# modular_expansion_system_audio_mixer.net
KiCad netlist of a schematic drawn in EAGLE
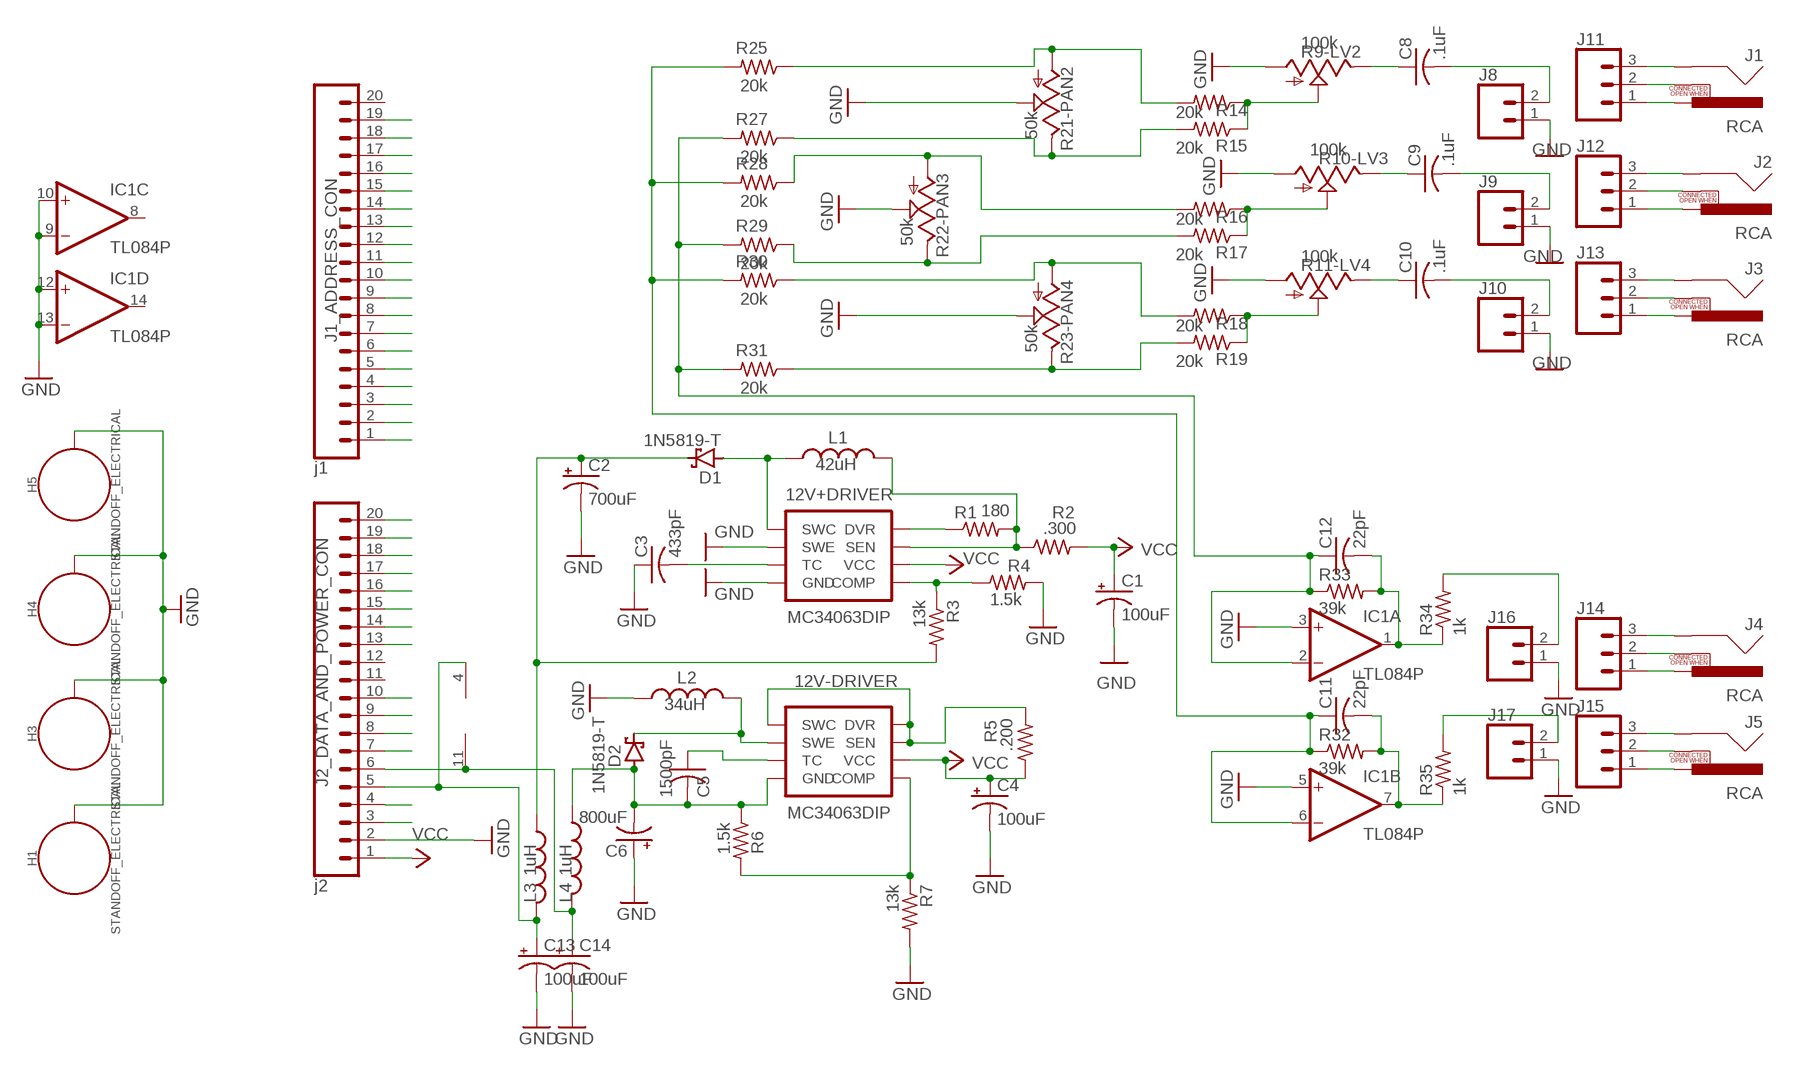
[diagram p0: schematic, sheet 1]

(export (version "E")
  (design (tool "Eeschema 10.0.6"))
  (components
    (comp (ref "12V+DRIVER")
      (value "MC34063DIP")
      (footprint "eagle-import:DIP-08")
      (libsource (lib "eagle-import") (part "MC34063DIP"))
    )
    (comp (ref "12V-DRIVER")
      (value "MC34063DIP")
      (footprint "eagle-import:DIP-08")
      (libsource (lib "eagle-import") (part "MC34063DIP"))
    )
    (comp (ref "C1")
      (value "100uF")
      (footprint "eagle-import:E2,5-5")
      (libsource (lib "eagle-import") (part "CPOL-USE2.5-5"))
    )
    (comp (ref "C2")
      (value "700uF")
      (footprint "eagle-import:E3,5-10")
      (libsource (lib "eagle-import") (part "CPOL-USE3.5-10"))
    )
    (comp (ref "C3")
      (value "433pF")
      (footprint "eagle-import:C025-040X050")
      (libsource (lib "eagle-import") (part "C-US025-040X050"))
    )
    (comp (ref "C4")
      (value "100uF")
      (footprint "eagle-import:E2,5-5")
      (libsource (lib "eagle-import") (part "CPOL-USE2.5-5"))
    )
    (comp (ref "C5")
      (value "1500pF")
      (footprint "eagle-import:C025-040X050")
      (libsource (lib "eagle-import") (part "C-US025-040X050"))
    )
    (comp (ref "C6")
      (value "800uF")
      (footprint "eagle-import:E3,5-10")
      (libsource (lib "eagle-import") (part "CPOL-USE3.5-10"))
    )
    (comp (ref "C8")
      (value ".1uF")
      (footprint "eagle-import:C025-024X044")
      (libsource (lib "eagle-import") (part "C-US025-024X044"))
    )
    (comp (ref "C9")
      (value ".1uF")
      (footprint "eagle-import:C025-024X044")
      (libsource (lib "eagle-import") (part "C-US025-024X044"))
    )
    (comp (ref "C10")
      (value ".1uF")
      (footprint "eagle-import:C025-024X044")
      (libsource (lib "eagle-import") (part "C-US025-024X044"))
    )
    (comp (ref "C11")
      (value "22pF")
      (footprint "eagle-import:C025-024X044")
      (libsource (lib "eagle-import") (part "C-US025-024X044"))
    )
    (comp (ref "C12")
      (value "22pF")
      (footprint "eagle-import:C025-024X044")
      (libsource (lib "eagle-import") (part "C-US025-024X044"))
    )
    (comp (ref "C13")
      (value "100uF")
      (footprint "eagle-import:E2,5-5")
      (libsource (lib "eagle-import") (part "CPOL-USE2.5-5"))
    )
    (comp (ref "C14")
      (value "100uF")
      (footprint "eagle-import:E2,5-5")
      (libsource (lib "eagle-import") (part "CPOL-USE2.5-5"))
    )
    (comp (ref "D1")
      (value "1N5819-T")
      (footprint "eagle-import:DO41-7.6")
      (libsource (lib "eagle-import") (part "1N5819-T"))
    )
    (comp (ref "D2")
      (value "1N5819-T")
      (footprint "eagle-import:DO41-7.6")
      (libsource (lib "eagle-import") (part "1N5819-T"))
    )
    (comp (ref "H1")
      (value "STANDOFF_ELECTRICAL")
      (footprint "eagle-import:STANDOFF-ELECTRICAL")
      (libsource (lib "eagle-import") (part "STANDOFF_ELECTRICAL"))
    )
    (comp (ref "H3")
      (value "STANDOFF_ELECTRICAL")
      (footprint "eagle-import:STANDOFF-ELECTRICAL")
      (libsource (lib "eagle-import") (part "STANDOFF_ELECTRICAL"))
    )
    (comp (ref "H4")
      (value "STANDOFF_ELECTRICAL")
      (footprint "eagle-import:STANDOFF-ELECTRICAL")
      (libsource (lib "eagle-import") (part "STANDOFF_ELECTRICAL"))
    )
    (comp (ref "H5")
      (value "STANDOFF_ELECTRICAL")
      (footprint "eagle-import:STANDOFF-ELECTRICAL")
      (libsource (lib "eagle-import") (part "STANDOFF_ELECTRICAL"))
    )
    (comp (ref "IC1")
      (value "TL084P")
      (footprint "eagle-import:DIL14")
      (libsource (lib "eagle-import") (part "TL084P"))
    )
    (comp (ref "J1")
      (value "RCA")
      (footprint "eagle-import:RCA")
      (libsource (lib "eagle-import") (part "RCA"))
    )
    (comp (ref "J1_ADDRESS_CON")
      (value "j1")
      (footprint "eagle-import:1X20")
      (libsource (lib "eagle-import") (part "CONN_20"))
    )
    (comp (ref "J2")
      (value "RCA")
      (footprint "eagle-import:RCA")
      (libsource (lib "eagle-import") (part "RCA"))
    )
    (comp (ref "J2_DATA_AND_POWER_CON")
      (value "j2")
      (footprint "eagle-import:1X20")
      (libsource (lib "eagle-import") (part "CONN_20"))
    )
    (comp (ref "J3")
      (value "RCA")
      (footprint "eagle-import:RCA")
      (libsource (lib "eagle-import") (part "RCA"))
    )
    (comp (ref "J4")
      (value "RCA")
      (footprint "eagle-import:RCA")
      (libsource (lib "eagle-import") (part "RCA"))
    )
    (comp (ref "J5")
      (value "RCA")
      (footprint "eagle-import:RCA")
      (libsource (lib "eagle-import") (part "RCA"))
    )
    (comp (ref "J8")
      (value "CONN_02")
      (footprint "eagle-import:1X02")
      (libsource (lib "eagle-import") (part "CONN_02"))
    )
    (comp (ref "J9")
      (value "CONN_02")
      (footprint "eagle-import:1X02")
      (libsource (lib "eagle-import") (part "CONN_02"))
    )
    (comp (ref "J10")
      (value "CONN_02")
      (footprint "eagle-import:1X02")
      (libsource (lib "eagle-import") (part "CONN_02"))
    )
    (comp (ref "J11")
      (value "CONN_03")
      (footprint "eagle-import:1X03")
      (libsource (lib "eagle-import") (part "CONN_03"))
    )
    (comp (ref "J12")
      (value "CONN_03")
      (footprint "eagle-import:1X03")
      (libsource (lib "eagle-import") (part "CONN_03"))
    )
    (comp (ref "J13")
      (value "CONN_03")
      (footprint "eagle-import:1X03")
      (libsource (lib "eagle-import") (part "CONN_03"))
    )
    (comp (ref "J14")
      (value "CONN_03")
      (footprint "eagle-import:1X03")
      (libsource (lib "eagle-import") (part "CONN_03"))
    )
    (comp (ref "J15")
      (value "CONN_03")
      (footprint "eagle-import:1X03")
      (libsource (lib "eagle-import") (part "CONN_03"))
    )
    (comp (ref "J16")
      (value "CONN_02")
      (footprint "eagle-import:1X02")
      (libsource (lib "eagle-import") (part "CONN_02"))
    )
    (comp (ref "J17")
      (value "CONN_02")
      (footprint "eagle-import:1X02")
      (libsource (lib "eagle-import") (part "CONN_02"))
    )
    (comp (ref "L1")
      (value "42uH")
      (footprint "eagle-import:0207_7")
      (libsource (lib "eagle-import") (part "resistor_348_L-US0207/7"))
    )
    (comp (ref "L2")
      (value "34uH")
      (footprint "eagle-import:0207_7")
      (libsource (lib "eagle-import") (part "resistor_348_L-US0207/7"))
    )
    (comp (ref "L3")
      (value "1uH")
      (footprint "eagle-import:0207_5V")
      (libsource (lib "eagle-import") (part "L-US0207/5V"))
    )
    (comp (ref "L4")
      (value "1uH")
      (footprint "eagle-import:0207_5V")
      (libsource (lib "eagle-import") (part "L-US0207/5V"))
    )
    (comp (ref "R1")
      (value "180")
      (footprint "eagle-import:0204V")
      (libsource (lib "eagle-import") (part "R-US_0204/2V"))
    )
    (comp (ref "R2")
      (value ".300")
      (footprint "eagle-import:0204V")
      (libsource (lib "eagle-import") (part "R-US_0204/2V"))
    )
    (comp (ref "R3")
      (value "13k")
      (footprint "eagle-import:0204V")
      (libsource (lib "eagle-import") (part "R-US_0204/2V"))
    )
    (comp (ref "R4")
      (value "1.5k")
      (footprint "eagle-import:0204V")
      (libsource (lib "eagle-import") (part "R-US_0204/2V"))
    )
    (comp (ref "R5")
      (value ".200")
      (footprint "eagle-import:0204V")
      (libsource (lib "eagle-import") (part "R-US_0204/2V"))
    )
    (comp (ref "R6")
      (value "1.5k")
      (footprint "eagle-import:0204V")
      (libsource (lib "eagle-import") (part "R-US_0204/2V"))
    )
    (comp (ref "R7")
      (value "13k")
      (footprint "eagle-import:0204V")
      (libsource (lib "eagle-import") (part "R-US_0204/2V"))
    )
    (comp (ref "R9-LV2")
      (value "100k")
      (footprint "eagle-import:B25U")
      (libsource (lib "eagle-import") (part "TRIM_US-B25U"))
    )
    (comp (ref "R10-LV3")
      (value "100k")
      (footprint "eagle-import:B25U")
      (libsource (lib "eagle-import") (part "TRIM_US-B25U"))
    )
    (comp (ref "R11-LV4")
      (value "100k")
      (footprint "eagle-import:B25U")
      (libsource (lib "eagle-import") (part "TRIM_US-B25U"))
    )
    (comp (ref "R14")
      (value "20k")
      (footprint "eagle-import:0204V")
      (libsource (lib "eagle-import") (part "R-US_0204/2V"))
    )
    (comp (ref "R15")
      (value "20k")
      (footprint "eagle-import:0204V")
      (libsource (lib "eagle-import") (part "R-US_0204/2V"))
    )
    (comp (ref "R16")
      (value "20k")
      (footprint "eagle-import:0204V")
      (libsource (lib "eagle-import") (part "R-US_0204/2V"))
    )
    (comp (ref "R17")
      (value "20k")
      (footprint "eagle-import:0204V")
      (libsource (lib "eagle-import") (part "R-US_0204/2V"))
    )
    (comp (ref "R18")
      (value "20k")
      (footprint "eagle-import:0204V")
      (libsource (lib "eagle-import") (part "R-US_0204/2V"))
    )
    (comp (ref "R19")
      (value "20k")
      (footprint "eagle-import:0204V")
      (libsource (lib "eagle-import") (part "R-US_0204/2V"))
    )
    (comp (ref "R21-PAN2")
      (value "50k")
      (footprint "eagle-import:B25U")
      (libsource (lib "eagle-import") (part "TRIM_US-B25U"))
    )
    (comp (ref "R22-PAN3")
      (value "50k")
      (footprint "eagle-import:B25U")
      (libsource (lib "eagle-import") (part "TRIM_US-B25U"))
    )
    (comp (ref "R23-PAN4")
      (value "50k")
      (footprint "eagle-import:B25U")
      (libsource (lib "eagle-import") (part "TRIM_US-B25U"))
    )
    (comp (ref "R25")
      (value "20k")
      (footprint "eagle-import:0204V")
      (libsource (lib "eagle-import") (part "R-US_0204/2V"))
    )
    (comp (ref "R27")
      (value "20k")
      (footprint "eagle-import:0204V")
      (libsource (lib "eagle-import") (part "R-US_0204/2V"))
    )
    (comp (ref "R28")
      (value "20k")
      (footprint "eagle-import:0204V")
      (libsource (lib "eagle-import") (part "R-US_0204/2V"))
    )
    (comp (ref "R29")
      (value "20k")
      (footprint "eagle-import:0204V")
      (libsource (lib "eagle-import") (part "R-US_0204/2V"))
    )
    (comp (ref "R30")
      (value "20k")
      (footprint "eagle-import:0204V")
      (libsource (lib "eagle-import") (part "R-US_0204/2V"))
    )
    (comp (ref "R31")
      (value "20k")
      (footprint "eagle-import:0204V")
      (libsource (lib "eagle-import") (part "R-US_0204/2V"))
    )
    (comp (ref "R32")
      (value "39k")
      (footprint "eagle-import:0204V")
      (libsource (lib "eagle-import") (part "R-US_0204/2V"))
    )
    (comp (ref "R33")
      (value "39k")
      (footprint "eagle-import:0204V")
      (libsource (lib "eagle-import") (part "R-US_0204/2V"))
    )
    (comp (ref "R34")
      (value "1k")
      (footprint "eagle-import:0204V")
      (libsource (lib "eagle-import") (part "R-US_0204/2V"))
    )
    (comp (ref "R35")
      (value "1k")
      (footprint "eagle-import:0204V")
      (libsource (lib "eagle-import") (part "R-US_0204/2V"))
    )
  )
  (nets
    (net (code "1") (name "GND") (class "Default")
      (node (ref "12V+DRIVER") (pin "2") (pinfunction "SWE_2") (pintype "bidirectional"))
      (node (ref "12V+DRIVER") (pin "4") (pinfunction "GND_4") (pintype "bidirectional"))
      (node (ref "C1") (pin "-") (pinfunction "-_-") (pintype "passive"))
      (node (ref "C13") (pin "-") (pinfunction "-_-") (pintype "passive"))
      (node (ref "C14") (pin "-") (pinfunction "-_-") (pintype "passive"))
      (node (ref "C2") (pin "-") (pinfunction "-_-") (pintype "passive"))
      (node (ref "C3") (pin "1") (pinfunction "1_1") (pintype "passive"))
      (node (ref "C4") (pin "-") (pinfunction "-_-") (pintype "passive"))
      (node (ref "C6") (pin "+") (pinfunction "+_+") (pintype "passive"))
      (node (ref "H1") (pin "P1") (pinfunction "P$1_P1") (pintype "bidirectional"))
      (node (ref "H3") (pin "P1") (pinfunction "P$1_P1") (pintype "bidirectional"))
      (node (ref "H4") (pin "P1") (pinfunction "P$1_P1") (pintype "bidirectional"))
      (node (ref "H5") (pin "P1") (pinfunction "P$1_P1") (pintype "bidirectional"))
      (node (ref "IC1") (pin "10") (pinfunction "+IN_10") (pintype "input"))
      (node (ref "IC1") (pin "12") (pinfunction "+IN_12") (pintype "input"))
      (node (ref "IC1") (pin "13") (pinfunction "-IN_13") (pintype "input"))
      (node (ref "IC1") (pin "3") (pinfunction "+IN_3") (pintype "input"))
      (node (ref "IC1") (pin "5") (pinfunction "+IN_5") (pintype "input"))
      (node (ref "IC1") (pin "9") (pinfunction "-IN_9") (pintype "input"))
      (node (ref "J10") (pin "1") (pinfunction "1_1") (pintype "passive"))
      (node (ref "J16") (pin "1") (pinfunction "1_1") (pintype "passive"))
      (node (ref "J17") (pin "1") (pinfunction "1_1") (pintype "passive"))
      (node (ref "J2_DATA_AND_POWER_CON") (pin "2") (pinfunction "2_2") (pintype "passive"))
      (node (ref "J8") (pin "1") (pinfunction "1_1") (pintype "passive"))
      (node (ref "J9") (pin "1") (pinfunction "1_1") (pintype "passive"))
      (node (ref "L2") (pin "1") (pinfunction "1_1") (pintype "passive"))
      (node (ref "R10-LV3") (pin "A") (pinfunction "A_A") (pintype "passive"))
      (node (ref "R11-LV4") (pin "A") (pinfunction "A_A") (pintype "passive"))
      (node (ref "R21-PAN2") (pin "S") (pinfunction "S_S") (pintype "passive"))
      (node (ref "R22-PAN3") (pin "S") (pinfunction "S_S") (pintype "passive"))
      (node (ref "R23-PAN4") (pin "S") (pinfunction "S_S") (pintype "passive"))
      (node (ref "R4") (pin "2") (pinfunction "2_2") (pintype "passive"))
      (node (ref "R7") (pin "2") (pinfunction "2_2") (pintype "passive"))
      (node (ref "R9-LV2") (pin "A") (pinfunction "A_A") (pintype "passive"))
    )
    (net (code "2") (name "Net-(12V+DRIVER-COMP)") (class "Default")
      (node (ref "12V+DRIVER") (pin "5") (pinfunction "COMP_5") (pintype "bidirectional"))
      (node (ref "R3") (pin "1") (pinfunction "1_1") (pintype "passive"))
      (node (ref "R4") (pin "1") (pinfunction "1_1") (pintype "passive"))
    )
    (net (code "3") (name "Net-(12V+DRIVER-DVR)") (class "Default")
      (node (ref "12V+DRIVER") (pin "8") (pinfunction "DVR_8") (pintype "bidirectional"))
      (node (ref "R1") (pin "1") (pinfunction "1_1") (pintype "passive"))
    )
    (net (code "4") (name "Net-(12V+DRIVER-SEN)") (class "Default")
      (node (ref "12V+DRIVER") (pin "7") (pinfunction "SEN_7") (pintype "bidirectional"))
      (node (ref "L1") (pin "2") (pinfunction "2_2") (pintype "passive"))
      (node (ref "R1") (pin "2") (pinfunction "2_2") (pintype "passive"))
      (node (ref "R2") (pin "1") (pinfunction "1_1") (pintype "passive"))
    )
    (net (code "5") (name "Net-(12V+DRIVER-SWC)") (class "Default")
      (node (ref "12V+DRIVER") (pin "1") (pinfunction "SWC_1") (pintype "bidirectional"))
      (node (ref "D1") (pin "A") (pinfunction "A_A") (pintype "passive"))
      (node (ref "L1") (pin "1") (pinfunction "1_1") (pintype "passive"))
    )
    (net (code "6") (name "Net-(12V+DRIVER-TC)") (class "Default")
      (node (ref "12V+DRIVER") (pin "3") (pinfunction "TC_3") (pintype "bidirectional"))
      (node (ref "C3") (pin "2") (pinfunction "2_2") (pintype "passive"))
    )
    (net (code "7") (name "Net-(12V-DRIVER-COMP)") (class "Default")
      (node (ref "12V-DRIVER") (pin "5") (pinfunction "COMP_5") (pintype "bidirectional"))
      (node (ref "R6") (pin "2") (pinfunction "2_2") (pintype "passive"))
      (node (ref "R7") (pin "1") (pinfunction "1_1") (pintype "passive"))
    )
    (net (code "8") (name "Net-(12V-DRIVER-DVR)") (class "Default")
      (node (ref "12V-DRIVER") (pin "1") (pinfunction "SWC_1") (pintype "bidirectional"))
      (node (ref "12V-DRIVER") (pin "7") (pinfunction "SEN_7") (pintype "bidirectional"))
      (node (ref "12V-DRIVER") (pin "8") (pinfunction "DVR_8") (pintype "bidirectional"))
      (node (ref "R5") (pin "2") (pinfunction "2_2") (pintype "passive"))
    )
    (net (code "9") (name "Net-(12V-DRIVER-GND)") (class "Default")
      (node (ref "12V-DRIVER") (pin "4") (pinfunction "GND_4") (pintype "bidirectional"))
      (node (ref "C5") (pin "2") (pinfunction "2_2") (pintype "passive"))
      (node (ref "C6") (pin "-") (pinfunction "-_-") (pintype "passive"))
      (node (ref "D2") (pin "A") (pinfunction "A_A") (pintype "passive"))
      (node (ref "L4") (pin "1") (pinfunction "1_1") (pintype "passive"))
      (node (ref "R6") (pin "1") (pinfunction "1_1") (pintype "passive"))
    )
    (net (code "10") (name "Net-(12V-DRIVER-SWE)") (class "Default")
      (node (ref "12V-DRIVER") (pin "2") (pinfunction "SWE_2") (pintype "bidirectional"))
      (node (ref "D2") (pin "C") (pinfunction "C_C") (pintype "passive"))
      (node (ref "L2") (pin "2") (pinfunction "2_2") (pintype "passive"))
    )
    (net (code "11") (name "Net-(12V-DRIVER-TC)") (class "Default")
      (node (ref "12V-DRIVER") (pin "3") (pinfunction "TC_3") (pintype "bidirectional"))
      (node (ref "C5") (pin "1") (pinfunction "1_1") (pintype "passive"))
    )
    (net (code "12") (name "Net-(C2-Pad+)") (class "Default")
      (node (ref "C2") (pin "+") (pinfunction "+_+") (pintype "passive"))
      (node (ref "D1") (pin "C") (pinfunction "C_C") (pintype "passive"))
      (node (ref "L3") (pin "1") (pinfunction "1_1") (pintype "passive"))
      (node (ref "R3") (pin "2") (pinfunction "2_2") (pintype "passive"))
    )
    (net (code "13") (name "Net-(C8-Pad1)") (class "Default")
      (node (ref "C8") (pin "1") (pinfunction "1_1") (pintype "passive"))
      (node (ref "R9-LV2") (pin "E") (pinfunction "E_E") (pintype "passive"))
    )
    (net (code "14") (name "Net-(C8-Pad2)") (class "Default")
      (node (ref "C8") (pin "2") (pinfunction "2_2") (pintype "passive"))
      (node (ref "J8") (pin "2") (pinfunction "2_2") (pintype "passive"))
    )
    (net (code "15") (name "Net-(C9-Pad1)") (class "Default")
      (node (ref "C9") (pin "1") (pinfunction "1_1") (pintype "passive"))
      (node (ref "R10-LV3") (pin "E") (pinfunction "E_E") (pintype "passive"))
    )
    (net (code "16") (name "Net-(C9-Pad2)") (class "Default")
      (node (ref "C9") (pin "2") (pinfunction "2_2") (pintype "passive"))
      (node (ref "J9") (pin "2") (pinfunction "2_2") (pintype "passive"))
    )
    (net (code "17") (name "Net-(C10-Pad1)") (class "Default")
      (node (ref "C10") (pin "1") (pinfunction "1_1") (pintype "passive"))
      (node (ref "R11-LV4") (pin "E") (pinfunction "E_E") (pintype "passive"))
    )
    (net (code "18") (name "Net-(C10-Pad2)") (class "Default")
      (node (ref "C10") (pin "2") (pinfunction "2_2") (pintype "passive"))
      (node (ref "J10") (pin "2") (pinfunction "2_2") (pintype "passive"))
    )
    (net (code "19") (name "Net-(IC1A--IN)") (class "Default")
      (node (ref "C12") (pin "1") (pinfunction "1_1") (pintype "passive"))
      (node (ref "IC1") (pin "2") (pinfunction "-IN_2") (pintype "input"))
      (node (ref "R27") (pin "2") (pinfunction "2_2") (pintype "passive"))
      (node (ref "R29") (pin "2") (pinfunction "2_2") (pintype "passive"))
      (node (ref "R31") (pin "2") (pinfunction "2_2") (pintype "passive"))
      (node (ref "R33") (pin "1") (pinfunction "1_1") (pintype "passive"))
    )
    (net (code "20") (name "Net-(IC1A-OUT)") (class "Default")
      (node (ref "C12") (pin "2") (pinfunction "2_2") (pintype "passive"))
      (node (ref "IC1") (pin "1") (pinfunction "OUT_1") (pintype "output"))
      (node (ref "R33") (pin "2") (pinfunction "2_2") (pintype "passive"))
      (node (ref "R34") (pin "1") (pinfunction "1_1") (pintype "passive"))
    )
    (net (code "21") (name "Net-(IC1B--IN)") (class "Default")
      (node (ref "C11") (pin "1") (pinfunction "1_1") (pintype "passive"))
      (node (ref "IC1") (pin "6") (pinfunction "-IN_6") (pintype "input"))
      (node (ref "R25") (pin "2") (pinfunction "2_2") (pintype "passive"))
      (node (ref "R28") (pin "2") (pinfunction "2_2") (pintype "passive"))
      (node (ref "R30") (pin "2") (pinfunction "2_2") (pintype "passive"))
      (node (ref "R32") (pin "1") (pinfunction "1_1") (pintype "passive"))
    )
    (net (code "22") (name "Net-(IC1B-OUT)") (class "Default")
      (node (ref "C11") (pin "2") (pinfunction "2_2") (pintype "passive"))
      (node (ref "IC1") (pin "7") (pinfunction "OUT_7") (pintype "output"))
      (node (ref "R32") (pin "2") (pinfunction "2_2") (pintype "passive"))
      (node (ref "R35") (pin "1") (pinfunction "1_1") (pintype "passive"))
    )
    (net (code "23") (name "Net-(IC1E-V+)") (class "Default")
      (node (ref "C13") (pin "+") (pinfunction "+_+") (pintype "passive"))
      (node (ref "IC1") (pin "4") (pinfunction "V+_4") (pintype "power_in"))
      (node (ref "J2_DATA_AND_POWER_CON") (pin "5") (pinfunction "5_5") (pintype "passive"))
      (node (ref "L3") (pin "2") (pinfunction "2_2") (pintype "passive"))
    )
    (net (code "24") (name "Net-(IC1E-V-)") (class "Default")
      (node (ref "C14") (pin "+") (pinfunction "+_+") (pintype "passive"))
      (node (ref "IC1") (pin "11") (pinfunction "V-_11") (pintype "power_in"))
      (node (ref "J2_DATA_AND_POWER_CON") (pin "6") (pinfunction "6_6") (pintype "passive"))
      (node (ref "L4") (pin "2") (pinfunction "2_2") (pintype "passive"))
    )
    (net (code "25") (name "Net-(J1-PadPIN)") (class "Default")
      (node (ref "J1") (pin "PIN") (pinfunction "PIN_PIN") (pintype "bidirectional"))
      (node (ref "J11") (pin "1") (pinfunction "1_1") (pintype "passive"))
    )
    (net (code "26") (name "Net-(J1-PadSHELL)") (class "Default")
      (node (ref "J1") (pin "SHELL") (pinfunction "SHELL_SHELL") (pintype "bidirectional"))
      (node (ref "J11") (pin "3") (pinfunction "3_3") (pintype "passive"))
    )
    (net (code "27") (name "Net-(J1-PadSWITCH)") (class "Default")
      (node (ref "J1") (pin "SWITCH") (pinfunction "SWITCH_SWITCH") (pintype "bidirectional"))
      (node (ref "J11") (pin "2") (pinfunction "2_2") (pintype "passive"))
    )
    (net (code "28") (name "Net-(J12-Pad1)") (class "Default")
      (node (ref "J12") (pin "1") (pinfunction "1_1") (pintype "passive"))
      (node (ref "J2") (pin "PIN") (pinfunction "PIN_PIN") (pintype "bidirectional"))
    )
    (net (code "29") (name "Net-(J12-Pad2)") (class "Default")
      (node (ref "J12") (pin "2") (pinfunction "2_2") (pintype "passive"))
      (node (ref "J2") (pin "SWITCH") (pinfunction "SWITCH_SWITCH") (pintype "bidirectional"))
    )
    (net (code "30") (name "Net-(J12-Pad3)") (class "Default")
      (node (ref "J12") (pin "3") (pinfunction "3_3") (pintype "passive"))
      (node (ref "J2") (pin "SHELL") (pinfunction "SHELL_SHELL") (pintype "bidirectional"))
    )
    (net (code "31") (name "Net-(J13-Pad1)") (class "Default")
      (node (ref "J13") (pin "1") (pinfunction "1_1") (pintype "passive"))
      (node (ref "J3") (pin "PIN") (pinfunction "PIN_PIN") (pintype "bidirectional"))
    )
    (net (code "32") (name "Net-(J13-Pad2)") (class "Default")
      (node (ref "J13") (pin "2") (pinfunction "2_2") (pintype "passive"))
      (node (ref "J3") (pin "SWITCH") (pinfunction "SWITCH_SWITCH") (pintype "bidirectional"))
    )
    (net (code "33") (name "Net-(J13-Pad3)") (class "Default")
      (node (ref "J13") (pin "3") (pinfunction "3_3") (pintype "passive"))
      (node (ref "J3") (pin "SHELL") (pinfunction "SHELL_SHELL") (pintype "bidirectional"))
    )
    (net (code "34") (name "Net-(J14-Pad1)") (class "Default")
      (node (ref "J14") (pin "1") (pinfunction "1_1") (pintype "passive"))
      (node (ref "J4") (pin "PIN") (pinfunction "PIN_PIN") (pintype "bidirectional"))
    )
    (net (code "35") (name "Net-(J14-Pad2)") (class "Default")
      (node (ref "J14") (pin "2") (pinfunction "2_2") (pintype "passive"))
      (node (ref "J4") (pin "SWITCH") (pinfunction "SWITCH_SWITCH") (pintype "bidirectional"))
    )
    (net (code "36") (name "Net-(J14-Pad3)") (class "Default")
      (node (ref "J14") (pin "3") (pinfunction "3_3") (pintype "passive"))
      (node (ref "J4") (pin "SHELL") (pinfunction "SHELL_SHELL") (pintype "bidirectional"))
    )
    (net (code "37") (name "Net-(J15-Pad1)") (class "Default")
      (node (ref "J15") (pin "1") (pinfunction "1_1") (pintype "passive"))
      (node (ref "J5") (pin "PIN") (pinfunction "PIN_PIN") (pintype "bidirectional"))
    )
    (net (code "38") (name "Net-(J15-Pad2)") (class "Default")
      (node (ref "J15") (pin "2") (pinfunction "2_2") (pintype "passive"))
      (node (ref "J5") (pin "SWITCH") (pinfunction "SWITCH_SWITCH") (pintype "bidirectional"))
    )
    (net (code "39") (name "Net-(J15-Pad3)") (class "Default")
      (node (ref "J15") (pin "3") (pinfunction "3_3") (pintype "passive"))
      (node (ref "J5") (pin "SHELL") (pinfunction "SHELL_SHELL") (pintype "bidirectional"))
    )
    (net (code "40") (name "Net-(J16-Pad2)") (class "Default")
      (node (ref "J16") (pin "2") (pinfunction "2_2") (pintype "passive"))
      (node (ref "R34") (pin "2") (pinfunction "2_2") (pintype "passive"))
    )
    (net (code "41") (name "Net-(J17-Pad2)") (class "Default")
      (node (ref "J17") (pin "2") (pinfunction "2_2") (pintype "passive"))
      (node (ref "R35") (pin "2") (pinfunction "2_2") (pintype "passive"))
    )
    (net (code "42") (name "Net-(R10-LV3-PadS)") (class "Default")
      (node (ref "R10-LV3") (pin "S") (pinfunction "S_S") (pintype "passive"))
      (node (ref "R16") (pin "1") (pinfunction "1_1") (pintype "passive"))
      (node (ref "R17") (pin "1") (pinfunction "1_1") (pintype "passive"))
    )
    (net (code "43") (name "Net-(R11-LV4-PadS)") (class "Default")
      (node (ref "R11-LV4") (pin "S") (pinfunction "S_S") (pintype "passive"))
      (node (ref "R18") (pin "1") (pinfunction "1_1") (pintype "passive"))
      (node (ref "R19") (pin "1") (pinfunction "1_1") (pintype "passive"))
    )
    (net (code "44") (name "Net-(R14-Pad1)") (class "Default")
      (node (ref "R14") (pin "1") (pinfunction "1_1") (pintype "passive"))
      (node (ref "R15") (pin "1") (pinfunction "1_1") (pintype "passive"))
      (node (ref "R9-LV2") (pin "S") (pinfunction "S_S") (pintype "passive"))
    )
    (net (code "45") (name "Net-(R14-Pad2)") (class "Default")
      (node (ref "R14") (pin "2") (pinfunction "2_2") (pintype "passive"))
      (node (ref "R21-PAN2") (pin "A") (pinfunction "A_A") (pintype "passive"))
      (node (ref "R25") (pin "1") (pinfunction "1_1") (pintype "passive"))
    )
    (net (code "46") (name "Net-(R15-Pad2)") (class "Default")
      (node (ref "R15") (pin "2") (pinfunction "2_2") (pintype "passive"))
      (node (ref "R21-PAN2") (pin "E") (pinfunction "E_E") (pintype "passive"))
      (node (ref "R27") (pin "1") (pinfunction "1_1") (pintype "passive"))
    )
    (net (code "47") (name "Net-(R16-Pad2)") (class "Default")
      (node (ref "R16") (pin "2") (pinfunction "2_2") (pintype "passive"))
      (node (ref "R22-PAN3") (pin "A") (pinfunction "A_A") (pintype "passive"))
      (node (ref "R28") (pin "1") (pinfunction "1_1") (pintype "passive"))
    )
    (net (code "48") (name "Net-(R17-Pad2)") (class "Default")
      (node (ref "R17") (pin "2") (pinfunction "2_2") (pintype "passive"))
      (node (ref "R22-PAN3") (pin "E") (pinfunction "E_E") (pintype "passive"))
      (node (ref "R29") (pin "1") (pinfunction "1_1") (pintype "passive"))
    )
    (net (code "49") (name "Net-(R18-Pad2)") (class "Default")
      (node (ref "R18") (pin "2") (pinfunction "2_2") (pintype "passive"))
      (node (ref "R23-PAN4") (pin "A") (pinfunction "A_A") (pintype "passive"))
      (node (ref "R30") (pin "1") (pinfunction "1_1") (pintype "passive"))
    )
    (net (code "50") (name "Net-(R19-Pad2)") (class "Default")
      (node (ref "R19") (pin "2") (pinfunction "2_2") (pintype "passive"))
      (node (ref "R23-PAN4") (pin "E") (pinfunction "E_E") (pintype "passive"))
      (node (ref "R31") (pin "1") (pinfunction "1_1") (pintype "passive"))
    )
    (net (code "51") (name "VCC") (class "Default")
      (node (ref "12V+DRIVER") (pin "6") (pinfunction "VCC_6") (pintype "bidirectional"))
      (node (ref "12V-DRIVER") (pin "6") (pinfunction "VCC_6") (pintype "bidirectional"))
      (node (ref "C1") (pin "+") (pinfunction "+_+") (pintype "passive"))
      (node (ref "C4") (pin "+") (pinfunction "+_+") (pintype "passive"))
      (node (ref "J2_DATA_AND_POWER_CON") (pin "1") (pinfunction "1_1") (pintype "passive"))
      (node (ref "R2") (pin "2") (pinfunction "2_2") (pintype "passive"))
      (node (ref "R5") (pin "1") (pinfunction "1_1") (pintype "passive"))
    )
    (net (code "52") (name "unconnected-(IC1C-OUT-Pad8)") (class "Default")
      (node (ref "IC1") (pin "8") (pinfunction "OUT_8") (pintype "output"))
    )
    (net (code "53") (name "unconnected-(IC1D-OUT-Pad14)") (class "Default")
      (node (ref "IC1") (pin "14") (pinfunction "OUT_14") (pintype "output"))
    )
    (net (code "54") (name "unconnected-(J1_ADDRESS_CON-Pad1)") (class "Default")
      (node (ref "J1_ADDRESS_CON") (pin "1") (pinfunction "1_1") (pintype "passive"))
    )
    (net (code "55") (name "unconnected-(J1_ADDRESS_CON-Pad2)") (class "Default")
      (node (ref "J1_ADDRESS_CON") (pin "2") (pinfunction "2_2") (pintype "passive"))
    )
    (net (code "56") (name "unconnected-(J1_ADDRESS_CON-Pad3)") (class "Default")
      (node (ref "J1_ADDRESS_CON") (pin "3") (pinfunction "3_3") (pintype "passive"))
    )
    (net (code "57") (name "unconnected-(J1_ADDRESS_CON-Pad4)") (class "Default")
      (node (ref "J1_ADDRESS_CON") (pin "4") (pinfunction "4_4") (pintype "passive"))
    )
    (net (code "58") (name "unconnected-(J1_ADDRESS_CON-Pad5)") (class "Default")
      (node (ref "J1_ADDRESS_CON") (pin "5") (pinfunction "5_5") (pintype "passive"))
    )
    (net (code "59") (name "unconnected-(J1_ADDRESS_CON-Pad6)") (class "Default")
      (node (ref "J1_ADDRESS_CON") (pin "6") (pinfunction "6_6") (pintype "passive"))
    )
    (net (code "60") (name "unconnected-(J1_ADDRESS_CON-Pad7)") (class "Default")
      (node (ref "J1_ADDRESS_CON") (pin "7") (pinfunction "7_7") (pintype "passive"))
    )
    (net (code "61") (name "unconnected-(J1_ADDRESS_CON-Pad8)") (class "Default")
      (node (ref "J1_ADDRESS_CON") (pin "8") (pinfunction "8_8") (pintype "passive"))
    )
    (net (code "62") (name "unconnected-(J1_ADDRESS_CON-Pad9)") (class "Default")
      (node (ref "J1_ADDRESS_CON") (pin "9") (pinfunction "9_9") (pintype "passive"))
    )
    (net (code "63") (name "unconnected-(J1_ADDRESS_CON-Pad10)") (class "Default")
      (node (ref "J1_ADDRESS_CON") (pin "10") (pinfunction "10_10") (pintype "passive"))
    )
    (net (code "64") (name "unconnected-(J1_ADDRESS_CON-Pad11)") (class "Default")
      (node (ref "J1_ADDRESS_CON") (pin "11") (pinfunction "11_11") (pintype "passive"))
    )
    (net (code "65") (name "unconnected-(J1_ADDRESS_CON-Pad12)") (class "Default")
      (node (ref "J1_ADDRESS_CON") (pin "12") (pinfunction "12_12") (pintype "passive"))
    )
    (net (code "66") (name "unconnected-(J1_ADDRESS_CON-Pad13)") (class "Default")
      (node (ref "J1_ADDRESS_CON") (pin "13") (pinfunction "13_13") (pintype "passive"))
    )
    (net (code "67") (name "unconnected-(J1_ADDRESS_CON-Pad14)") (class "Default")
      (node (ref "J1_ADDRESS_CON") (pin "14") (pinfunction "14_14") (pintype "passive"))
    )
    (net (code "68") (name "unconnected-(J1_ADDRESS_CON-Pad15)") (class "Default")
      (node (ref "J1_ADDRESS_CON") (pin "15") (pinfunction "15_15") (pintype "passive"))
    )
    (net (code "69") (name "unconnected-(J1_ADDRESS_CON-Pad16)") (class "Default")
      (node (ref "J1_ADDRESS_CON") (pin "16") (pinfunction "16_16") (pintype "passive"))
    )
    (net (code "70") (name "unconnected-(J1_ADDRESS_CON-Pad17)") (class "Default")
      (node (ref "J1_ADDRESS_CON") (pin "17") (pinfunction "17_17") (pintype "passive"))
    )
    (net (code "71") (name "unconnected-(J1_ADDRESS_CON-Pad18)") (class "Default")
      (node (ref "J1_ADDRESS_CON") (pin "18") (pinfunction "18_18") (pintype "passive"))
    )
    (net (code "72") (name "unconnected-(J1_ADDRESS_CON-Pad19)") (class "Default")
      (node (ref "J1_ADDRESS_CON") (pin "19") (pinfunction "19_19") (pintype "passive"))
    )
    (net (code "73") (name "unconnected-(J1_ADDRESS_CON-Pad20)") (class "Default")
      (node (ref "J1_ADDRESS_CON") (pin "20") (pinfunction "20_20") (pintype "passive"))
    )
    (net (code "74") (name "unconnected-(J2_DATA_AND_POWER_CON-Pad3)") (class "Default")
      (node (ref "J2_DATA_AND_POWER_CON") (pin "3") (pinfunction "3_3") (pintype "passive"))
    )
    (net (code "75") (name "unconnected-(J2_DATA_AND_POWER_CON-Pad4)") (class "Default")
      (node (ref "J2_DATA_AND_POWER_CON") (pin "4") (pinfunction "4_4") (pintype "passive"))
    )
    (net (code "76") (name "unconnected-(J2_DATA_AND_POWER_CON-Pad7)") (class "Default")
      (node (ref "J2_DATA_AND_POWER_CON") (pin "7") (pinfunction "7_7") (pintype "passive"))
    )
    (net (code "77") (name "unconnected-(J2_DATA_AND_POWER_CON-Pad8)") (class "Default")
      (node (ref "J2_DATA_AND_POWER_CON") (pin "8") (pinfunction "8_8") (pintype "passive"))
    )
    (net (code "78") (name "unconnected-(J2_DATA_AND_POWER_CON-Pad9)") (class "Default")
      (node (ref "J2_DATA_AND_POWER_CON") (pin "9") (pinfunction "9_9") (pintype "passive"))
    )
    (net (code "79") (name "unconnected-(J2_DATA_AND_POWER_CON-Pad10)") (class "Default")
      (node (ref "J2_DATA_AND_POWER_CON") (pin "10") (pinfunction "10_10") (pintype "passive"))
    )
    (net (code "80") (name "unconnected-(J2_DATA_AND_POWER_CON-Pad11)") (class "Default")
      (node (ref "J2_DATA_AND_POWER_CON") (pin "11") (pinfunction "11_11") (pintype "passive"))
    )
    (net (code "81") (name "unconnected-(J2_DATA_AND_POWER_CON-Pad12)") (class "Default")
      (node (ref "J2_DATA_AND_POWER_CON") (pin "12") (pinfunction "12_12") (pintype "passive"))
    )
    (net (code "82") (name "unconnected-(J2_DATA_AND_POWER_CON-Pad13)") (class "Default")
      (node (ref "J2_DATA_AND_POWER_CON") (pin "13") (pinfunction "13_13") (pintype "passive"))
    )
    (net (code "83") (name "unconnected-(J2_DATA_AND_POWER_CON-Pad14)") (class "Default")
      (node (ref "J2_DATA_AND_POWER_CON") (pin "14") (pinfunction "14_14") (pintype "passive"))
    )
    (net (code "84") (name "unconnected-(J2_DATA_AND_POWER_CON-Pad15)") (class "Default")
      (node (ref "J2_DATA_AND_POWER_CON") (pin "15") (pinfunction "15_15") (pintype "passive"))
    )
    (net (code "85") (name "unconnected-(J2_DATA_AND_POWER_CON-Pad16)") (class "Default")
      (node (ref "J2_DATA_AND_POWER_CON") (pin "16") (pinfunction "16_16") (pintype "passive"))
    )
    (net (code "86") (name "unconnected-(J2_DATA_AND_POWER_CON-Pad17)") (class "Default")
      (node (ref "J2_DATA_AND_POWER_CON") (pin "17") (pinfunction "17_17") (pintype "passive"))
    )
    (net (code "87") (name "unconnected-(J2_DATA_AND_POWER_CON-Pad18)") (class "Default")
      (node (ref "J2_DATA_AND_POWER_CON") (pin "18") (pinfunction "18_18") (pintype "passive"))
    )
    (net (code "88") (name "unconnected-(J2_DATA_AND_POWER_CON-Pad19)") (class "Default")
      (node (ref "J2_DATA_AND_POWER_CON") (pin "19") (pinfunction "19_19") (pintype "passive"))
    )
    (net (code "89") (name "unconnected-(J2_DATA_AND_POWER_CON-Pad20)") (class "Default")
      (node (ref "J2_DATA_AND_POWER_CON") (pin "20") (pinfunction "20_20") (pintype "passive"))
    )
  )
)
